# Balancing_FETs.net
KiCad netlist of a schematic drawn in Altium Designer
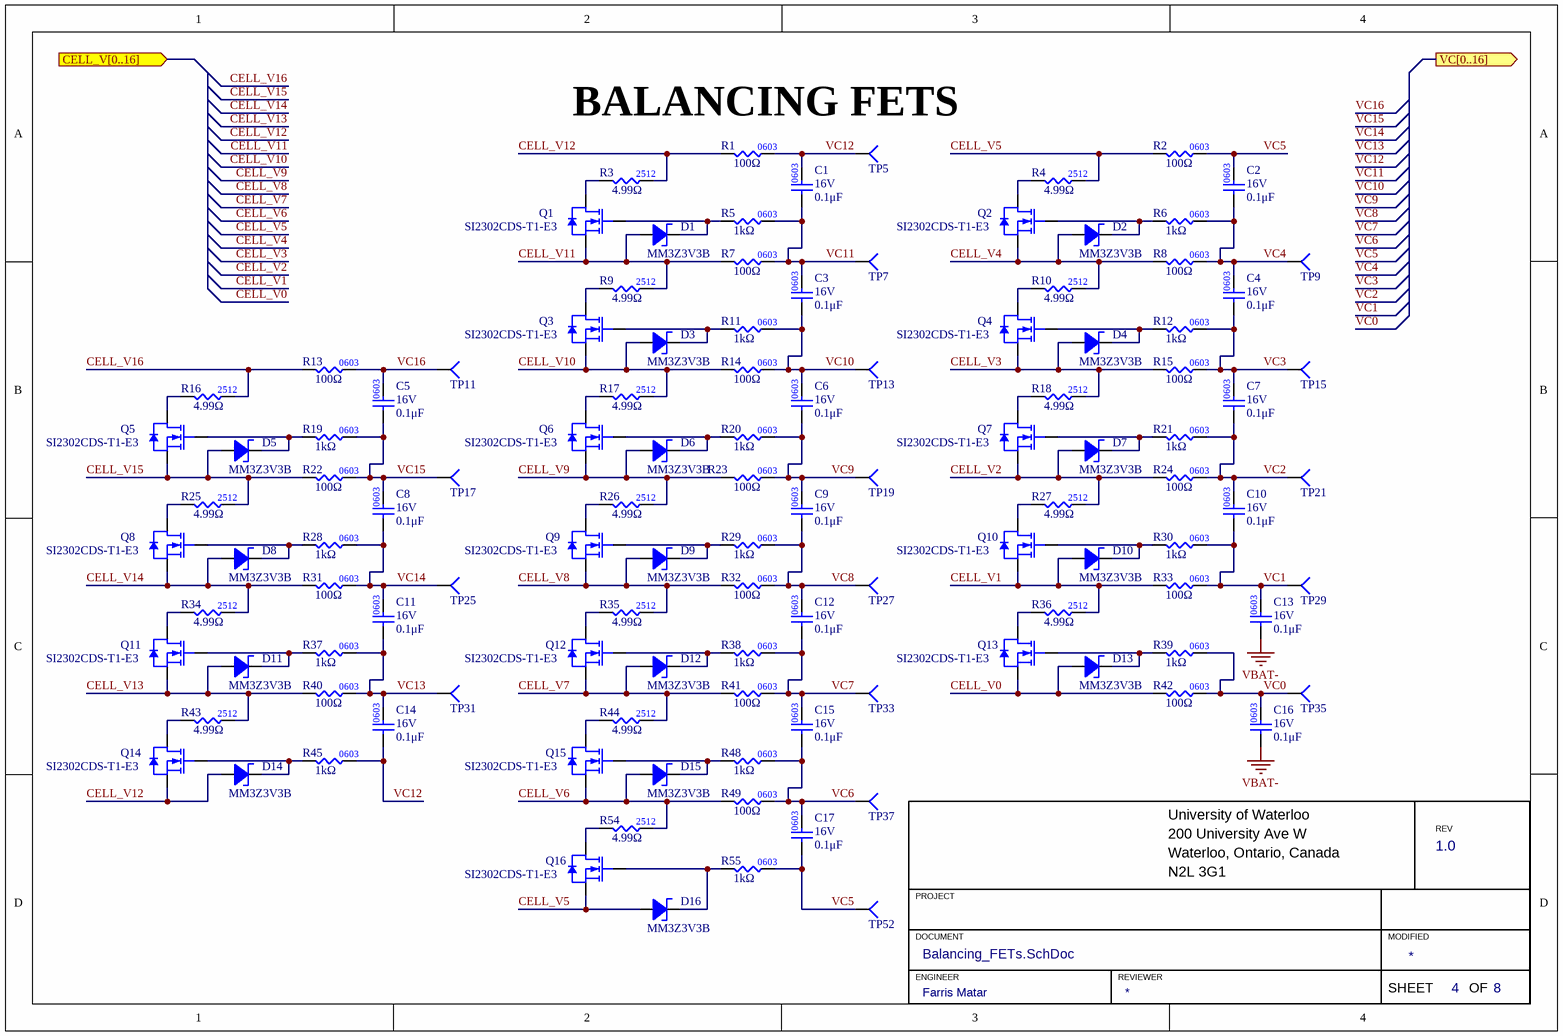
[diagram p0: Balancing_FETs.SchDoc]

(export (version "E")
  (design (tool "Eeschema 10.0.6"))
  (components
    (comp (ref "C1")
      (value "0.1μF")
      (footprint "CAP0603")
      (description "CAP CER 0.1UF 16V X7R 0603")
      (fields (field (name "VOLTAGE RATING") "16V") (field (name "Comment") "CAP_0.1uF_16V_0603"))
      (libsource (lib "Personal_Schematic_Library_2022") (part "CAP_0.1uF_16V_0603"))
    )
    (comp (ref "C2")
      (value "0.1μF")
      (footprint "CAP0603")
      (description "CAP CER 0.1UF 16V X7R 0603")
      (fields (field (name "VOLTAGE RATING") "16V") (field (name "Comment") "CAP_0.1uF_16V_0603"))
      (libsource (lib "Personal_Schematic_Library_2022") (part "CAP_0.1uF_16V_0603"))
    )
    (comp (ref "C3")
      (value "0.1μF")
      (footprint "CAP0603")
      (description "CAP CER 0.1UF 16V X7R 0603")
      (fields (field (name "VOLTAGE RATING") "16V") (field (name "Comment") "CAP_0.1uF_16V_0603"))
      (libsource (lib "Personal_Schematic_Library_2022") (part "CAP_0.1uF_16V_0603"))
    )
    (comp (ref "C4")
      (value "0.1μF")
      (footprint "CAP0603")
      (description "CAP CER 0.1UF 16V X7R 0603")
      (fields (field (name "VOLTAGE RATING") "16V") (field (name "Comment") "CAP_0.1uF_16V_0603"))
      (libsource (lib "Personal_Schematic_Library_2022") (part "CAP_0.1uF_16V_0603"))
    )
    (comp (ref "C5")
      (value "0.1μF")
      (footprint "CAP0603")
      (description "CAP CER 0.1UF 16V X7R 0603")
      (fields (field (name "VOLTAGE RATING") "16V") (field (name "Comment") "CAP_0.1uF_16V_0603"))
      (libsource (lib "Personal_Schematic_Library_2022") (part "CAP_0.1uF_16V_0603"))
    )
    (comp (ref "C6")
      (value "0.1μF")
      (footprint "CAP0603")
      (description "CAP CER 0.1UF 16V X7R 0603")
      (fields (field (name "VOLTAGE RATING") "16V") (field (name "Comment") "CAP_0.1uF_16V_0603"))
      (libsource (lib "Personal_Schematic_Library_2022") (part "CAP_0.1uF_16V_0603"))
    )
    (comp (ref "C7")
      (value "0.1μF")
      (footprint "CAP0603")
      (description "CAP CER 0.1UF 16V X7R 0603")
      (fields (field (name "VOLTAGE RATING") "16V") (field (name "Comment") "CAP_0.1uF_16V_0603"))
      (libsource (lib "Personal_Schematic_Library_2022") (part "CAP_0.1uF_16V_0603"))
    )
    (comp (ref "C8")
      (value "0.1μF")
      (footprint "CAP0603")
      (description "CAP CER 0.1UF 16V X7R 0603")
      (fields (field (name "VOLTAGE RATING") "16V") (field (name "Comment") "CAP_0.1uF_16V_0603"))
      (libsource (lib "Personal_Schematic_Library_2022") (part "CAP_0.1uF_16V_0603"))
    )
    (comp (ref "C9")
      (value "0.1μF")
      (footprint "CAP0603")
      (description "CAP CER 0.1UF 16V X7R 0603")
      (fields (field (name "VOLTAGE RATING") "16V") (field (name "Comment") "CAP_0.1uF_16V_0603"))
      (libsource (lib "Personal_Schematic_Library_2022") (part "CAP_0.1uF_16V_0603"))
    )
    (comp (ref "C10")
      (value "0.1μF")
      (footprint "CAP0603")
      (description "CAP CER 0.1UF 16V X7R 0603")
      (fields (field (name "VOLTAGE RATING") "16V") (field (name "Comment") "CAP_0.1uF_16V_0603"))
      (libsource (lib "Personal_Schematic_Library_2022") (part "CAP_0.1uF_16V_0603"))
    )
    (comp (ref "C11")
      (value "0.1μF")
      (footprint "CAP0603")
      (description "CAP CER 0.1UF 16V X7R 0603")
      (fields (field (name "VOLTAGE RATING") "16V") (field (name "Comment") "CAP_0.1uF_16V_0603"))
      (libsource (lib "Personal_Schematic_Library_2022") (part "CAP_0.1uF_16V_0603"))
    )
    (comp (ref "C12")
      (value "0.1μF")
      (footprint "CAP0603")
      (description "CAP CER 0.1UF 16V X7R 0603")
      (fields (field (name "VOLTAGE RATING") "16V") (field (name "Comment") "CAP_0.1uF_16V_0603"))
      (libsource (lib "Personal_Schematic_Library_2022") (part "CAP_0.1uF_16V_0603"))
    )
    (comp (ref "C13")
      (value "0.1μF")
      (footprint "CAP0603")
      (description "CAP CER 0.1UF 16V X7R 0603")
      (fields (field (name "VOLTAGE RATING") "16V") (field (name "Comment") "CAP_0.1uF_16V_0603"))
      (libsource (lib "Personal_Schematic_Library_2022") (part "CAP_0.1uF_16V_0603"))
    )
    (comp (ref "C14")
      (value "0.1μF")
      (footprint "CAP0603")
      (description "CAP CER 0.1UF 16V X7R 0603")
      (fields (field (name "VOLTAGE RATING") "16V") (field (name "Comment") "CAP_0.1uF_16V_0603"))
      (libsource (lib "Personal_Schematic_Library_2022") (part "CAP_0.1uF_16V_0603"))
    )
    (comp (ref "C15")
      (value "0.1μF")
      (footprint "CAP0603")
      (description "CAP CER 0.1UF 16V X7R 0603")
      (fields (field (name "VOLTAGE RATING") "16V") (field (name "Comment") "CAP_0.1uF_16V_0603"))
      (libsource (lib "Personal_Schematic_Library_2022") (part "CAP_0.1uF_16V_0603"))
    )
    (comp (ref "C16")
      (value "0.1μF")
      (footprint "CAP0603")
      (description "CAP CER 0.1UF 16V X7R 0603")
      (fields (field (name "VOLTAGE RATING") "16V") (field (name "Comment") "CAP_0.1uF_16V_0603"))
      (libsource (lib "Personal_Schematic_Library_2022") (part "CAP_0.1uF_16V_0603"))
    )
    (comp (ref "C17")
      (value "0.1μF")
      (footprint "CAP0603")
      (description "CAP CER 0.1UF 16V X7R 0603")
      (fields (field (name "VOLTAGE RATING") "16V") (field (name "Comment") "CAP_0.1uF_16V_0603"))
      (libsource (lib "Personal_Schematic_Library_2022") (part "CAP_0.1uF_16V_0603"))
    )
    (comp (ref "D1")
      (value "DIO_ZENER_3V3")
      (footprint "DIO_ZENER_3V3")
      (description "DIODE ZENER 3.3V 200mW SOD323F")
      (fields (field (name "MANUFACTURER PART NUMBER 1") "MM3Z3V3B"))
      (libsource (lib "Personal_Schematic_Library_2022") (part "DIO_ZENER_3V3"))
    )
    (comp (ref "D2")
      (value "DIO_ZENER_3V3")
      (footprint "DIO_ZENER_3V3")
      (description "DIODE ZENER 3.3V 200mW SOD323F")
      (fields (field (name "MANUFACTURER PART NUMBER 1") "MM3Z3V3B"))
      (libsource (lib "Personal_Schematic_Library_2022") (part "DIO_ZENER_3V3"))
    )
    (comp (ref "D3")
      (value "DIO_ZENER_3V3")
      (footprint "DIO_ZENER_3V3")
      (description "DIODE ZENER 3.3V 200mW SOD323F")
      (fields (field (name "MANUFACTURER PART NUMBER 1") "MM3Z3V3B"))
      (libsource (lib "Personal_Schematic_Library_2022") (part "DIO_ZENER_3V3"))
    )
    (comp (ref "D4")
      (value "DIO_ZENER_3V3")
      (footprint "DIO_ZENER_3V3")
      (description "DIODE ZENER 3.3V 200mW SOD323F")
      (fields (field (name "MANUFACTURER PART NUMBER 1") "MM3Z3V3B"))
      (libsource (lib "Personal_Schematic_Library_2022") (part "DIO_ZENER_3V3"))
    )
    (comp (ref "D5")
      (value "DIO_ZENER_3V3")
      (footprint "DIO_ZENER_3V3")
      (description "DIODE ZENER 3.3V 200mW SOD323F")
      (fields (field (name "MANUFACTURER PART NUMBER 1") "MM3Z3V3B"))
      (libsource (lib "Personal_Schematic_Library_2022") (part "DIO_ZENER_3V3"))
    )
    (comp (ref "D6")
      (value "DIO_ZENER_3V3")
      (footprint "DIO_ZENER_3V3")
      (description "DIODE ZENER 3.3V 200mW SOD323F")
      (fields (field (name "MANUFACTURER PART NUMBER 1") "MM3Z3V3B"))
      (libsource (lib "Personal_Schematic_Library_2022") (part "DIO_ZENER_3V3"))
    )
    (comp (ref "D7")
      (value "DIO_ZENER_3V3")
      (footprint "DIO_ZENER_3V3")
      (description "DIODE ZENER 3.3V 200mW SOD323F")
      (fields (field (name "MANUFACTURER PART NUMBER 1") "MM3Z3V3B"))
      (libsource (lib "Personal_Schematic_Library_2022") (part "DIO_ZENER_3V3"))
    )
    (comp (ref "D8")
      (value "DIO_ZENER_3V3")
      (footprint "DIO_ZENER_3V3")
      (description "DIODE ZENER 3.3V 200mW SOD323F")
      (fields (field (name "MANUFACTURER PART NUMBER 1") "MM3Z3V3B"))
      (libsource (lib "Personal_Schematic_Library_2022") (part "DIO_ZENER_3V3"))
    )
    (comp (ref "D9")
      (value "DIO_ZENER_3V3")
      (footprint "DIO_ZENER_3V3")
      (description "DIODE ZENER 3.3V 200mW SOD323F")
      (fields (field (name "MANUFACTURER PART NUMBER 1") "MM3Z3V3B"))
      (libsource (lib "Personal_Schematic_Library_2022") (part "DIO_ZENER_3V3"))
    )
    (comp (ref "D10")
      (value "DIO_ZENER_3V3")
      (footprint "DIO_ZENER_3V3")
      (description "DIODE ZENER 3.3V 200mW SOD323F")
      (fields (field (name "MANUFACTURER PART NUMBER 1") "MM3Z3V3B"))
      (libsource (lib "Personal_Schematic_Library_2022") (part "DIO_ZENER_3V3"))
    )
    (comp (ref "D11")
      (value "DIO_ZENER_3V3")
      (footprint "DIO_ZENER_3V3")
      (description "DIODE ZENER 3.3V 200mW SOD323F")
      (fields (field (name "MANUFACTURER PART NUMBER 1") "MM3Z3V3B"))
      (libsource (lib "Personal_Schematic_Library_2022") (part "DIO_ZENER_3V3"))
    )
    (comp (ref "D12")
      (value "DIO_ZENER_3V3")
      (footprint "DIO_ZENER_3V3")
      (description "DIODE ZENER 3.3V 200mW SOD323F")
      (fields (field (name "MANUFACTURER PART NUMBER 1") "MM3Z3V3B"))
      (libsource (lib "Personal_Schematic_Library_2022") (part "DIO_ZENER_3V3"))
    )
    (comp (ref "D13")
      (value "DIO_ZENER_3V3")
      (footprint "DIO_ZENER_3V3")
      (description "DIODE ZENER 3.3V 200mW SOD323F")
      (fields (field (name "MANUFACTURER PART NUMBER 1") "MM3Z3V3B"))
      (libsource (lib "Personal_Schematic_Library_2022") (part "DIO_ZENER_3V3"))
    )
    (comp (ref "D14")
      (value "DIO_ZENER_3V3")
      (footprint "DIO_ZENER_3V3")
      (description "DIODE ZENER 3.3V 200mW SOD323F")
      (fields (field (name "MANUFACTURER PART NUMBER 1") "MM3Z3V3B"))
      (libsource (lib "Personal_Schematic_Library_2022") (part "DIO_ZENER_3V3"))
    )
    (comp (ref "D15")
      (value "DIO_ZENER_3V3")
      (footprint "DIO_ZENER_3V3")
      (description "DIODE ZENER 3.3V 200mW SOD323F")
      (fields (field (name "MANUFACTURER PART NUMBER 1") "MM3Z3V3B"))
      (libsource (lib "Personal_Schematic_Library_2022") (part "DIO_ZENER_3V3"))
    )
    (comp (ref "D16")
      (value "DIO_ZENER_3V3")
      (footprint "DIO_ZENER_3V3")
      (description "DIODE ZENER 3.3V 200mW SOD323F")
      (fields (field (name "MANUFACTURER PART NUMBER 1") "MM3Z3V3B"))
      (libsource (lib "Personal_Schematic_Library_2022") (part "DIO_ZENER_3V3"))
    )
    (comp (ref "Q1")
      (value "NMOS_20V_6A")
      (footprint "SOT23-3")
      (description "MOSFET N-CH 20V 2.6A SOT23-3")
      (fields (field (name "MANUFACTURER PART NUMBER 1") "SI2302CDS-T1-E3"))
      (libsource (lib "Personal_Schematic_Library_2022") (part "NMOS_20V_2.6A"))
    )
    (comp (ref "Q2")
      (value "NMOS_20V_6A")
      (footprint "SOT23-3")
      (description "MOSFET N-CH 20V 2.6A SOT23-3")
      (fields (field (name "MANUFACTURER PART NUMBER 1") "SI2302CDS-T1-E3"))
      (libsource (lib "Personal_Schematic_Library_2022") (part "NMOS_20V_2.6A"))
    )
    (comp (ref "Q3")
      (value "NMOS_20V_6A")
      (footprint "SOT23-3")
      (description "MOSFET N-CH 20V 2.6A SOT23-3")
      (fields (field (name "MANUFACTURER PART NUMBER 1") "SI2302CDS-T1-E3"))
      (libsource (lib "Personal_Schematic_Library_2022") (part "NMOS_20V_2.6A"))
    )
    (comp (ref "Q4")
      (value "NMOS_20V_6A")
      (footprint "SOT23-3")
      (description "MOSFET N-CH 20V 2.6A SOT23-3")
      (fields (field (name "MANUFACTURER PART NUMBER 1") "SI2302CDS-T1-E3"))
      (libsource (lib "Personal_Schematic_Library_2022") (part "NMOS_20V_2.6A"))
    )
    (comp (ref "Q5")
      (value "NMOS_20V_6A")
      (footprint "SOT23-3")
      (description "MOSFET N-CH 20V 2.6A SOT23-3")
      (fields (field (name "MANUFACTURER PART NUMBER 1") "SI2302CDS-T1-E3"))
      (libsource (lib "Personal_Schematic_Library_2022") (part "NMOS_20V_2.6A"))
    )
    (comp (ref "Q6")
      (value "NMOS_20V_6A")
      (footprint "SOT23-3")
      (description "MOSFET N-CH 20V 2.6A SOT23-3")
      (fields (field (name "MANUFACTURER PART NUMBER 1") "SI2302CDS-T1-E3"))
      (libsource (lib "Personal_Schematic_Library_2022") (part "NMOS_20V_2.6A"))
    )
    (comp (ref "Q7")
      (value "NMOS_20V_6A")
      (footprint "SOT23-3")
      (description "MOSFET N-CH 20V 2.6A SOT23-3")
      (fields (field (name "MANUFACTURER PART NUMBER 1") "SI2302CDS-T1-E3"))
      (libsource (lib "Personal_Schematic_Library_2022") (part "NMOS_20V_2.6A"))
    )
    (comp (ref "Q8")
      (value "NMOS_20V_6A")
      (footprint "SOT23-3")
      (description "MOSFET N-CH 20V 2.6A SOT23-3")
      (fields (field (name "MANUFACTURER PART NUMBER 1") "SI2302CDS-T1-E3"))
      (libsource (lib "Personal_Schematic_Library_2022") (part "NMOS_20V_2.6A"))
    )
    (comp (ref "Q9")
      (value "NMOS_20V_6A")
      (footprint "SOT23-3")
      (description "MOSFET N-CH 20V 2.6A SOT23-3")
      (fields (field (name "MANUFACTURER PART NUMBER 1") "SI2302CDS-T1-E3"))
      (libsource (lib "Personal_Schematic_Library_2022") (part "NMOS_20V_2.6A"))
    )
    (comp (ref "Q10")
      (value "NMOS_20V_6A")
      (footprint "SOT23-3")
      (description "MOSFET N-CH 20V 2.6A SOT23-3")
      (fields (field (name "MANUFACTURER PART NUMBER 1") "SI2302CDS-T1-E3"))
      (libsource (lib "Personal_Schematic_Library_2022") (part "NMOS_20V_2.6A"))
    )
    (comp (ref "Q11")
      (value "NMOS_20V_6A")
      (footprint "SOT23-3")
      (description "MOSFET N-CH 20V 2.6A SOT23-3")
      (fields (field (name "MANUFACTURER PART NUMBER 1") "SI2302CDS-T1-E3"))
      (libsource (lib "Personal_Schematic_Library_2022") (part "NMOS_20V_2.6A"))
    )
    (comp (ref "Q12")
      (value "NMOS_20V_6A")
      (footprint "SOT23-3")
      (description "MOSFET N-CH 20V 2.6A SOT23-3")
      (fields (field (name "MANUFACTURER PART NUMBER 1") "SI2302CDS-T1-E3"))
      (libsource (lib "Personal_Schematic_Library_2022") (part "NMOS_20V_2.6A"))
    )
    (comp (ref "Q13")
      (value "NMOS_20V_6A")
      (footprint "SOT23-3")
      (description "MOSFET N-CH 20V 2.6A SOT23-3")
      (fields (field (name "MANUFACTURER PART NUMBER 1") "SI2302CDS-T1-E3"))
      (libsource (lib "Personal_Schematic_Library_2022") (part "NMOS_20V_2.6A"))
    )
    (comp (ref "Q14")
      (value "NMOS_20V_6A")
      (footprint "SOT23-3")
      (description "MOSFET N-CH 20V 2.6A SOT23-3")
      (fields (field (name "MANUFACTURER PART NUMBER 1") "SI2302CDS-T1-E3"))
      (libsource (lib "Personal_Schematic_Library_2022") (part "NMOS_20V_2.6A"))
    )
    (comp (ref "Q15")
      (value "NMOS_20V_6A")
      (footprint "SOT23-3")
      (description "MOSFET N-CH 20V 2.6A SOT23-3")
      (fields (field (name "MANUFACTURER PART NUMBER 1") "SI2302CDS-T1-E3"))
      (libsource (lib "Personal_Schematic_Library_2022") (part "NMOS_20V_2.6A"))
    )
    (comp (ref "Q16")
      (value "NMOS_20V_6A")
      (footprint "SOT23-3")
      (description "MOSFET N-CH 20V 2.6A SOT23-3")
      (fields (field (name "MANUFACTURER PART NUMBER 1") "SI2302CDS-T1-E3"))
      (libsource (lib "Personal_Schematic_Library_2022") (part "NMOS_20V_2.6A"))
    )
    (comp (ref "R1")
      (value "100Ω")
      (footprint "RES0603")
      (description "RES 100 OHM 1% 1/10W 0603")
      (fields (field (name "Comment") "RES_100Ω_0603_1%"))
      (libsource (lib "Personal_Schematic_Library_2022") (part "RES_100Ω_0603_1%"))
    )
    (comp (ref "R2")
      (value "100Ω")
      (footprint "RES0603")
      (description "RES 100 OHM 1% 1/10W 0603")
      (fields (field (name "Comment") "RES_100Ω_0603_1%"))
      (libsource (lib "Personal_Schematic_Library_2022") (part "RES_100Ω_0603_1%"))
    )
    (comp (ref "R3")
      (value "4.99Ω")
      (footprint "RES2512")
      (description "RES 4.99 OHM 1% 2W 2512")
      (fields (field (name "Comment") "RES_4.99Ω_2512_1%"))
      (libsource (lib "Personal_Schematic_Library_2022") (part "RES_4.99Ω_2512_1%"))
    )
    (comp (ref "R4")
      (value "4.99Ω")
      (footprint "RES2512")
      (description "RES 4.99 OHM 1% 2W 2512")
      (fields (field (name "Comment") "RES_4.99Ω_2512_1%"))
      (libsource (lib "Personal_Schematic_Library_2022") (part "RES_4.99Ω_2512_1%"))
    )
    (comp (ref "R5")
      (value "1kΩ")
      (footprint "RES0603")
      (description "RES 1K OHM 1% 1/8W 0603")
      (fields (field (name "Comment") "RES_1kΩ_0603_1%"))
      (libsource (lib "Personal_Schematic_Library_2022") (part "RES_1kΩ_0603_1%"))
    )
    (comp (ref "R6")
      (value "1kΩ")
      (footprint "RES0603")
      (description "RES 1K OHM 1% 1/8W 0603")
      (fields (field (name "Comment") "RES_1kΩ_0603_1%"))
      (libsource (lib "Personal_Schematic_Library_2022") (part "RES_1kΩ_0603_1%"))
    )
    (comp (ref "R7")
      (value "100Ω")
      (footprint "RES0603")
      (description "RES 100 OHM 1% 1/10W 0603")
      (fields (field (name "Comment") "RES_100Ω_0603_1%"))
      (libsource (lib "Personal_Schematic_Library_2022") (part "RES_100Ω_0603_1%"))
    )
    (comp (ref "R8")
      (value "100Ω")
      (footprint "RES0603")
      (description "RES 100 OHM 1% 1/10W 0603")
      (fields (field (name "Comment") "RES_100Ω_0603_1%"))
      (libsource (lib "Personal_Schematic_Library_2022") (part "RES_100Ω_0603_1%"))
    )
    (comp (ref "R9")
      (value "4.99Ω")
      (footprint "RES2512")
      (description "RES 4.99 OHM 1% 2W 2512")
      (fields (field (name "Comment") "RES_4.99Ω_2512_1%"))
      (libsource (lib "Personal_Schematic_Library_2022") (part "RES_4.99Ω_2512_1%"))
    )
    (comp (ref "R10")
      (value "4.99Ω")
      (footprint "RES2512")
      (description "RES 4.99 OHM 1% 2W 2512")
      (fields (field (name "Comment") "RES_4.99Ω_2512_1%"))
      (libsource (lib "Personal_Schematic_Library_2022") (part "RES_4.99Ω_2512_1%"))
    )
    (comp (ref "R11")
      (value "1kΩ")
      (footprint "RES0603")
      (description "RES 1K OHM 1% 1/8W 0603")
      (fields (field (name "Comment") "RES_1kΩ_0603_1%"))
      (libsource (lib "Personal_Schematic_Library_2022") (part "RES_1kΩ_0603_1%"))
    )
    (comp (ref "R12")
      (value "1kΩ")
      (footprint "RES0603")
      (description "RES 1K OHM 1% 1/8W 0603")
      (fields (field (name "Comment") "RES_1kΩ_0603_1%"))
      (libsource (lib "Personal_Schematic_Library_2022") (part "RES_1kΩ_0603_1%"))
    )
    (comp (ref "R13")
      (value "100Ω")
      (footprint "RES0603")
      (description "RES 100 OHM 1% 1/10W 0603")
      (fields (field (name "Comment") "RES_100Ω_0603_1%"))
      (libsource (lib "Personal_Schematic_Library_2022") (part "RES_100Ω_0603_1%"))
    )
    (comp (ref "R14")
      (value "100Ω")
      (footprint "RES0603")
      (description "RES 100 OHM 1% 1/10W 0603")
      (fields (field (name "Comment") "RES_100Ω_0603_1%"))
      (libsource (lib "Personal_Schematic_Library_2022") (part "RES_100Ω_0603_1%"))
    )
    (comp (ref "R15")
      (value "100Ω")
      (footprint "RES0603")
      (description "RES 100 OHM 1% 1/10W 0603")
      (fields (field (name "Comment") "RES_100Ω_0603_1%"))
      (libsource (lib "Personal_Schematic_Library_2022") (part "RES_100Ω_0603_1%"))
    )
    (comp (ref "R16")
      (value "4.99Ω")
      (footprint "RES2512")
      (description "RES 4.99 OHM 1% 2W 2512")
      (fields (field (name "Comment") "RES_4.99Ω_2512_1%"))
      (libsource (lib "Personal_Schematic_Library_2022") (part "RES_4.99Ω_2512_1%"))
    )
    (comp (ref "R17")
      (value "4.99Ω")
      (footprint "RES2512")
      (description "RES 4.99 OHM 1% 2W 2512")
      (fields (field (name "Comment") "RES_4.99Ω_2512_1%"))
      (libsource (lib "Personal_Schematic_Library_2022") (part "RES_4.99Ω_2512_1%"))
    )
    (comp (ref "R18")
      (value "4.99Ω")
      (footprint "RES2512")
      (description "RES 4.99 OHM 1% 2W 2512")
      (fields (field (name "Comment") "RES_4.99Ω_2512_1%"))
      (libsource (lib "Personal_Schematic_Library_2022") (part "RES_4.99Ω_2512_1%"))
    )
    (comp (ref "R19")
      (value "1kΩ")
      (footprint "RES0603")
      (description "RES 1K OHM 1% 1/8W 0603")
      (fields (field (name "Comment") "RES_1kΩ_0603_1%"))
      (libsource (lib "Personal_Schematic_Library_2022") (part "RES_1kΩ_0603_1%"))
    )
    (comp (ref "R20")
      (value "1kΩ")
      (footprint "RES0603")
      (description "RES 1K OHM 1% 1/8W 0603")
      (fields (field (name "Comment") "RES_1kΩ_0603_1%"))
      (libsource (lib "Personal_Schematic_Library_2022") (part "RES_1kΩ_0603_1%"))
    )
    (comp (ref "R21")
      (value "1kΩ")
      (footprint "RES0603")
      (description "RES 1K OHM 1% 1/8W 0603")
      (fields (field (name "Comment") "RES_1kΩ_0603_1%"))
      (libsource (lib "Personal_Schematic_Library_2022") (part "RES_1kΩ_0603_1%"))
    )
    (comp (ref "R22")
      (value "100Ω")
      (footprint "RES0603")
      (description "RES 100 OHM 1% 1/10W 0603")
      (fields (field (name "Comment") "RES_100Ω_0603_1%"))
      (libsource (lib "Personal_Schematic_Library_2022") (part "RES_100Ω_0603_1%"))
    )
    (comp (ref "R23")
      (value "100Ω")
      (footprint "RES0603")
      (description "RES 100 OHM 1% 1/10W 0603")
      (fields (field (name "Comment") "RES_100Ω_0603_1%"))
      (libsource (lib "Personal_Schematic_Library_2022") (part "RES_100Ω_0603_1%"))
    )
    (comp (ref "R24")
      (value "100Ω")
      (footprint "RES0603")
      (description "RES 100 OHM 1% 1/10W 0603")
      (fields (field (name "Comment") "RES_100Ω_0603_1%"))
      (libsource (lib "Personal_Schematic_Library_2022") (part "RES_100Ω_0603_1%"))
    )
    (comp (ref "R25")
      (value "4.99Ω")
      (footprint "RES2512")
      (description "RES 4.99 OHM 1% 2W 2512")
      (fields (field (name "Comment") "RES_4.99Ω_2512_1%"))
      (libsource (lib "Personal_Schematic_Library_2022") (part "RES_4.99Ω_2512_1%"))
    )
    (comp (ref "R26")
      (value "4.99Ω")
      (footprint "RES2512")
      (description "RES 4.99 OHM 1% 2W 2512")
      (fields (field (name "Comment") "RES_4.99Ω_2512_1%"))
      (libsource (lib "Personal_Schematic_Library_2022") (part "RES_4.99Ω_2512_1%"))
    )
    (comp (ref "R27")
      (value "4.99Ω")
      (footprint "RES2512")
      (description "RES 4.99 OHM 1% 2W 2512")
      (fields (field (name "Comment") "RES_4.99Ω_2512_1%"))
      (libsource (lib "Personal_Schematic_Library_2022") (part "RES_4.99Ω_2512_1%"))
    )
    (comp (ref "R28")
      (value "1kΩ")
      (footprint "RES0603")
      (description "RES 1K OHM 1% 1/8W 0603")
      (fields (field (name "Comment") "RES_1kΩ_0603_1%"))
      (libsource (lib "Personal_Schematic_Library_2022") (part "RES_1kΩ_0603_1%"))
    )
    (comp (ref "R29")
      (value "1kΩ")
      (footprint "RES0603")
      (description "RES 1K OHM 1% 1/8W 0603")
      (fields (field (name "Comment") "RES_1kΩ_0603_1%"))
      (libsource (lib "Personal_Schematic_Library_2022") (part "RES_1kΩ_0603_1%"))
    )
    (comp (ref "R30")
      (value "1kΩ")
      (footprint "RES0603")
      (description "RES 1K OHM 1% 1/8W 0603")
      (fields (field (name "Comment") "RES_1kΩ_0603_1%"))
      (libsource (lib "Personal_Schematic_Library_2022") (part "RES_1kΩ_0603_1%"))
    )
    (comp (ref "R31")
      (value "100Ω")
      (footprint "RES0603")
      (description "RES 100 OHM 1% 1/10W 0603")
      (fields (field (name "Comment") "RES_100Ω_0603_1%"))
      (libsource (lib "Personal_Schematic_Library_2022") (part "RES_100Ω_0603_1%"))
    )
    (comp (ref "R32")
      (value "100Ω")
      (footprint "RES0603")
      (description "RES 100 OHM 1% 1/10W 0603")
      (fields (field (name "Comment") "RES_100Ω_0603_1%"))
      (libsource (lib "Personal_Schematic_Library_2022") (part "RES_100Ω_0603_1%"))
    )
    (comp (ref "R33")
      (value "100Ω")
      (footprint "RES0603")
      (description "RES 100 OHM 1% 1/10W 0603")
      (fields (field (name "Comment") "RES_100Ω_0603_1%"))
      (libsource (lib "Personal_Schematic_Library_2022") (part "RES_100Ω_0603_1%"))
    )
    (comp (ref "R34")
      (value "4.99Ω")
      (footprint "RES2512")
      (description "RES 4.99 OHM 1% 2W 2512")
      (fields (field (name "Comment") "RES_4.99Ω_2512_1%"))
      (libsource (lib "Personal_Schematic_Library_2022") (part "RES_4.99Ω_2512_1%"))
    )
    (comp (ref "R35")
      (value "4.99Ω")
      (footprint "RES2512")
      (description "RES 4.99 OHM 1% 2W 2512")
      (fields (field (name "Comment") "RES_4.99Ω_2512_1%"))
      (libsource (lib "Personal_Schematic_Library_2022") (part "RES_4.99Ω_2512_1%"))
    )
    (comp (ref "R36")
      (value "4.99Ω")
      (footprint "RES2512")
      (description "RES 4.99 OHM 1% 2W 2512")
      (fields (field (name "Comment") "RES_4.99Ω_2512_1%"))
      (libsource (lib "Personal_Schematic_Library_2022") (part "RES_4.99Ω_2512_1%"))
    )
    (comp (ref "R37")
      (value "1kΩ")
      (footprint "RES0603")
      (description "RES 1K OHM 1% 1/8W 0603")
      (fields (field (name "Comment") "RES_1kΩ_0603_1%"))
      (libsource (lib "Personal_Schematic_Library_2022") (part "RES_1kΩ_0603_1%"))
    )
    (comp (ref "R38")
      (value "1kΩ")
      (footprint "RES0603")
      (description "RES 1K OHM 1% 1/8W 0603")
      (fields (field (name "Comment") "RES_1kΩ_0603_1%"))
      (libsource (lib "Personal_Schematic_Library_2022") (part "RES_1kΩ_0603_1%"))
    )
    (comp (ref "R39")
      (value "1kΩ")
      (footprint "RES0603")
      (description "RES 1K OHM 1% 1/8W 0603")
      (fields (field (name "Comment") "RES_1kΩ_0603_1%"))
      (libsource (lib "Personal_Schematic_Library_2022") (part "RES_1kΩ_0603_1%"))
    )
    (comp (ref "R40")
      (value "100Ω")
      (footprint "RES0603")
      (description "RES 100 OHM 1% 1/10W 0603")
      (fields (field (name "Comment") "RES_100Ω_0603_1%"))
      (libsource (lib "Personal_Schematic_Library_2022") (part "RES_100Ω_0603_1%"))
    )
    (comp (ref "R41")
      (value "100Ω")
      (footprint "RES0603")
      (description "RES 100 OHM 1% 1/10W 0603")
      (fields (field (name "Comment") "RES_100Ω_0603_1%"))
      (libsource (lib "Personal_Schematic_Library_2022") (part "RES_100Ω_0603_1%"))
    )
    (comp (ref "R42")
      (value "100Ω")
      (footprint "RES0603")
      (description "RES 100 OHM 1% 1/10W 0603")
      (fields (field (name "Comment") "RES_100Ω_0603_1%"))
      (libsource (lib "Personal_Schematic_Library_2022") (part "RES_100Ω_0603_1%"))
    )
    (comp (ref "R43")
      (value "4.99Ω")
      (footprint "RES2512")
      (description "RES 4.99 OHM 1% 2W 2512")
      (fields (field (name "Comment") "RES_4.99Ω_2512_1%"))
      (libsource (lib "Personal_Schematic_Library_2022") (part "RES_4.99Ω_2512_1%"))
    )
    (comp (ref "R44")
      (value "4.99Ω")
      (footprint "RES2512")
      (description "RES 4.99 OHM 1% 2W 2512")
      (fields (field (name "Comment") "RES_4.99Ω_2512_1%"))
      (libsource (lib "Personal_Schematic_Library_2022") (part "RES_4.99Ω_2512_1%"))
    )
    (comp (ref "R45")
      (value "1kΩ")
      (footprint "RES0603")
      (description "RES 1K OHM 1% 1/8W 0603")
      (fields (field (name "Comment") "RES_1kΩ_0603_1%"))
      (libsource (lib "Personal_Schematic_Library_2022") (part "RES_1kΩ_0603_1%"))
    )
    (comp (ref "R48")
      (value "1kΩ")
      (footprint "RES0603")
      (description "RES 1K OHM 1% 1/8W 0603")
      (fields (field (name "Comment") "RES_1kΩ_0603_1%"))
      (libsource (lib "Personal_Schematic_Library_2022") (part "RES_1kΩ_0603_1%"))
    )
    (comp (ref "R49")
      (value "100Ω")
      (footprint "RES0603")
      (description "RES 100 OHM 1% 1/10W 0603")
      (fields (field (name "Comment") "RES_100Ω_0603_1%"))
      (libsource (lib "Personal_Schematic_Library_2022") (part "RES_100Ω_0603_1%"))
    )
    (comp (ref "R54")
      (value "4.99Ω")
      (footprint "RES2512")
      (description "RES 4.99 OHM 1% 2W 2512")
      (fields (field (name "Comment") "RES_4.99Ω_2512_1%"))
      (libsource (lib "Personal_Schematic_Library_2022") (part "RES_4.99Ω_2512_1%"))
    )
    (comp (ref "R55")
      (value "1kΩ")
      (footprint "RES0603")
      (description "RES 1K OHM 1% 1/8W 0603")
      (fields (field (name "Comment") "RES_1kΩ_0603_1%"))
      (libsource (lib "Personal_Schematic_Library_2022") (part "RES_1kΩ_0603_1%"))
    )
    (comp (ref "TP5")
      (value "TESTPOINT_1MM_SQUARE")
      (footprint "TESTPOINT_SQUARE_1MM")
      (description "TESTPOINT 1MM SQUARE")
      (libsource (lib "Personal_Schematic_Library_2022") (part "TESTPOINT_1MM_SQUARE"))
    )
    (comp (ref "TP7")
      (value "TESTPOINT_1MM_SQUARE")
      (footprint "TESTPOINT_SQUARE_1MM")
      (description "TESTPOINT 1MM SQUARE")
      (libsource (lib "Personal_Schematic_Library_2022") (part "TESTPOINT_1MM_SQUARE"))
    )
    (comp (ref "TP9")
      (value "TESTPOINT_1MM_SQUARE")
      (footprint "TESTPOINT_SQUARE_1MM")
      (description "TESTPOINT 1MM SQUARE")
      (libsource (lib "Personal_Schematic_Library_2022") (part "TESTPOINT_1MM_SQUARE"))
    )
    (comp (ref "TP11")
      (value "TESTPOINT_1MM_SQUARE")
      (footprint "TESTPOINT_SQUARE_1MM")
      (description "TESTPOINT 1MM SQUARE")
      (libsource (lib "Personal_Schematic_Library_2022") (part "TESTPOINT_1MM_SQUARE"))
    )
    (comp (ref "TP13")
      (value "TESTPOINT_1MM_SQUARE")
      (footprint "TESTPOINT_SQUARE_1MM")
      (description "TESTPOINT 1MM SQUARE")
      (libsource (lib "Personal_Schematic_Library_2022") (part "TESTPOINT_1MM_SQUARE"))
    )
    (comp (ref "TP15")
      (value "TESTPOINT_1MM_SQUARE")
      (footprint "TESTPOINT_SQUARE_1MM")
      (description "TESTPOINT 1MM SQUARE")
      (libsource (lib "Personal_Schematic_Library_2022") (part "TESTPOINT_1MM_SQUARE"))
    )
    (comp (ref "TP17")
      (value "TESTPOINT_1MM_SQUARE")
      (footprint "TESTPOINT_SQUARE_1MM")
      (description "TESTPOINT 1MM SQUARE")
      (libsource (lib "Personal_Schematic_Library_2022") (part "TESTPOINT_1MM_SQUARE"))
    )
    (comp (ref "TP19")
      (value "TESTPOINT_1MM_SQUARE")
      (footprint "TESTPOINT_SQUARE_1MM")
      (description "TESTPOINT 1MM SQUARE")
      (libsource (lib "Personal_Schematic_Library_2022") (part "TESTPOINT_1MM_SQUARE"))
    )
    (comp (ref "TP21")
      (value "TESTPOINT_1MM_SQUARE")
      (footprint "TESTPOINT_SQUARE_1MM")
      (description "TESTPOINT 1MM SQUARE")
      (libsource (lib "Personal_Schematic_Library_2022") (part "TESTPOINT_1MM_SQUARE"))
    )
    (comp (ref "TP25")
      (value "TESTPOINT_1MM_SQUARE")
      (footprint "TESTPOINT_SQUARE_1MM")
      (description "TESTPOINT 1MM SQUARE")
      (libsource (lib "Personal_Schematic_Library_2022") (part "TESTPOINT_1MM_SQUARE"))
    )
    (comp (ref "TP27")
      (value "TESTPOINT_1MM_SQUARE")
      (footprint "TESTPOINT_SQUARE_1MM")
      (description "TESTPOINT 1MM SQUARE")
      (libsource (lib "Personal_Schematic_Library_2022") (part "TESTPOINT_1MM_SQUARE"))
    )
    (comp (ref "TP29")
      (value "TESTPOINT_1MM_SQUARE")
      (footprint "TESTPOINT_SQUARE_1MM")
      (description "TESTPOINT 1MM SQUARE")
      (libsource (lib "Personal_Schematic_Library_2022") (part "TESTPOINT_1MM_SQUARE"))
    )
    (comp (ref "TP31")
      (value "TESTPOINT_1MM_SQUARE")
      (footprint "TESTPOINT_SQUARE_1MM")
      (description "TESTPOINT 1MM SQUARE")
      (libsource (lib "Personal_Schematic_Library_2022") (part "TESTPOINT_1MM_SQUARE"))
    )
    (comp (ref "TP33")
      (value "TESTPOINT_1MM_SQUARE")
      (footprint "TESTPOINT_SQUARE_1MM")
      (description "TESTPOINT 1MM SQUARE")
      (libsource (lib "Personal_Schematic_Library_2022") (part "TESTPOINT_1MM_SQUARE"))
    )
    (comp (ref "TP35")
      (value "TESTPOINT_1MM_SQUARE")
      (footprint "TESTPOINT_SQUARE_1MM")
      (description "TESTPOINT 1MM SQUARE")
      (libsource (lib "Personal_Schematic_Library_2022") (part "TESTPOINT_1MM_SQUARE"))
    )
    (comp (ref "TP37")
      (value "TESTPOINT_1MM_SQUARE")
      (footprint "TESTPOINT_SQUARE_1MM")
      (description "TESTPOINT 1MM SQUARE")
      (libsource (lib "Personal_Schematic_Library_2022") (part "TESTPOINT_1MM_SQUARE"))
    )
    (comp (ref "TP52")
      (value "TESTPOINT_1MM_SQUARE")
      (footprint "TESTPOINT_SQUARE_1MM")
      (description "TESTPOINT 1MM SQUARE")
      (libsource (lib "Personal_Schematic_Library_2022") (part "TESTPOINT_1MM_SQUARE"))
    )
  )
  (nets
    (net (code "1") (name "/CELL_V0") (class "Default")
      (node (ref "D13") (pin "1") (pinfunction "Anode_1") (pintype "passive"))
      (node (ref "Q13") (pin "2") (pinfunction "SOURCE_2") (pintype "passive"))
      (node (ref "R42") (pin "1") (pinfunction "1_1") (pintype "passive"))
    )
    (net (code "2") (name "/CELL_V1") (class "Default")
      (node (ref "D10") (pin "1") (pinfunction "Anode_1") (pintype "passive"))
      (node (ref "Q10") (pin "2") (pinfunction "SOURCE_2") (pintype "passive"))
      (node (ref "R33") (pin "1") (pinfunction "1_1") (pintype "passive"))
      (node (ref "R36") (pin "2") (pinfunction "2_2") (pintype "passive"))
    )
    (net (code "3") (name "/CELL_V2") (class "Default")
      (node (ref "D7") (pin "1") (pinfunction "Anode_1") (pintype "passive"))
      (node (ref "Q7") (pin "2") (pinfunction "SOURCE_2") (pintype "passive"))
      (node (ref "R24") (pin "1") (pinfunction "1_1") (pintype "passive"))
      (node (ref "R27") (pin "2") (pinfunction "2_2") (pintype "passive"))
    )
    (net (code "4") (name "/CELL_V3") (class "Default")
      (node (ref "D4") (pin "1") (pinfunction "Anode_1") (pintype "passive"))
      (node (ref "Q4") (pin "2") (pinfunction "SOURCE_2") (pintype "passive"))
      (node (ref "R15") (pin "1") (pinfunction "1_1") (pintype "passive"))
      (node (ref "R18") (pin "2") (pinfunction "2_2") (pintype "passive"))
    )
    (net (code "5") (name "/CELL_V4") (class "Default")
      (node (ref "D2") (pin "1") (pinfunction "Anode_1") (pintype "passive"))
      (node (ref "Q2") (pin "2") (pinfunction "SOURCE_2") (pintype "passive"))
      (node (ref "R10") (pin "2") (pinfunction "2_2") (pintype "passive"))
      (node (ref "R8") (pin "1") (pinfunction "1_1") (pintype "passive"))
    )
    (net (code "6") (name "/CELL_V5") (class "Default")
      (node (ref "D16") (pin "1") (pinfunction "Anode_1") (pintype "passive"))
      (node (ref "Q16") (pin "2") (pinfunction "SOURCE_2") (pintype "passive"))
      (node (ref "R2") (pin "1") (pinfunction "1_1") (pintype "passive"))
      (node (ref "R4") (pin "2") (pinfunction "2_2") (pintype "passive"))
    )
    (net (code "7") (name "/CELL_V6") (class "Default")
      (node (ref "D15") (pin "1") (pinfunction "Anode_1") (pintype "passive"))
      (node (ref "Q15") (pin "2") (pinfunction "SOURCE_2") (pintype "passive"))
      (node (ref "R49") (pin "1") (pinfunction "1_1") (pintype "passive"))
      (node (ref "R54") (pin "2") (pinfunction "2_2") (pintype "passive"))
    )
    (net (code "8") (name "/CELL_V7") (class "Default")
      (node (ref "D12") (pin "1") (pinfunction "Anode_1") (pintype "passive"))
      (node (ref "Q12") (pin "2") (pinfunction "SOURCE_2") (pintype "passive"))
      (node (ref "R41") (pin "1") (pinfunction "1_1") (pintype "passive"))
      (node (ref "R44") (pin "2") (pinfunction "2_2") (pintype "passive"))
    )
    (net (code "9") (name "/CELL_V8") (class "Default")
      (node (ref "D9") (pin "1") (pinfunction "Anode_1") (pintype "passive"))
      (node (ref "Q9") (pin "2") (pinfunction "SOURCE_2") (pintype "passive"))
      (node (ref "R32") (pin "1") (pinfunction "1_1") (pintype "passive"))
      (node (ref "R35") (pin "2") (pinfunction "2_2") (pintype "passive"))
    )
    (net (code "10") (name "/CELL_V9") (class "Default")
      (node (ref "D6") (pin "1") (pinfunction "Anode_1") (pintype "passive"))
      (node (ref "Q6") (pin "2") (pinfunction "SOURCE_2") (pintype "passive"))
      (node (ref "R23") (pin "1") (pinfunction "1_1") (pintype "passive"))
      (node (ref "R26") (pin "2") (pinfunction "2_2") (pintype "passive"))
    )
    (net (code "11") (name "/CELL_V10") (class "Default")
      (node (ref "D3") (pin "1") (pinfunction "Anode_1") (pintype "passive"))
      (node (ref "Q3") (pin "2") (pinfunction "SOURCE_2") (pintype "passive"))
      (node (ref "R14") (pin "1") (pinfunction "1_1") (pintype "passive"))
      (node (ref "R17") (pin "2") (pinfunction "2_2") (pintype "passive"))
    )
    (net (code "12") (name "/CELL_V11") (class "Default")
      (node (ref "D1") (pin "1") (pinfunction "Anode_1") (pintype "passive"))
      (node (ref "Q1") (pin "2") (pinfunction "SOURCE_2") (pintype "passive"))
      (node (ref "R7") (pin "1") (pinfunction "1_1") (pintype "passive"))
      (node (ref "R9") (pin "2") (pinfunction "2_2") (pintype "passive"))
    )
    (net (code "13") (name "/CELL_V12") (class "Default")
      (node (ref "D14") (pin "1") (pinfunction "Anode_1") (pintype "passive"))
      (node (ref "Q14") (pin "2") (pinfunction "SOURCE_2") (pintype "passive"))
      (node (ref "R1") (pin "1") (pinfunction "1_1") (pintype "passive"))
      (node (ref "R3") (pin "2") (pinfunction "2_2") (pintype "passive"))
    )
    (net (code "14") (name "/CELL_V13") (class "Default")
      (node (ref "D11") (pin "1") (pinfunction "Anode_1") (pintype "passive"))
      (node (ref "Q11") (pin "2") (pinfunction "SOURCE_2") (pintype "passive"))
      (node (ref "R40") (pin "1") (pinfunction "1_1") (pintype "passive"))
      (node (ref "R43") (pin "2") (pinfunction "2_2") (pintype "passive"))
    )
    (net (code "15") (name "/CELL_V14") (class "Default")
      (node (ref "D8") (pin "1") (pinfunction "Anode_1") (pintype "passive"))
      (node (ref "Q8") (pin "2") (pinfunction "SOURCE_2") (pintype "passive"))
      (node (ref "R31") (pin "1") (pinfunction "1_1") (pintype "passive"))
      (node (ref "R34") (pin "2") (pinfunction "2_2") (pintype "passive"))
    )
    (net (code "16") (name "/CELL_V15") (class "Default")
      (node (ref "D5") (pin "1") (pinfunction "Anode_1") (pintype "passive"))
      (node (ref "Q5") (pin "2") (pinfunction "SOURCE_2") (pintype "passive"))
      (node (ref "R22") (pin "1") (pinfunction "1_1") (pintype "passive"))
      (node (ref "R25") (pin "2") (pinfunction "2_2") (pintype "passive"))
    )
    (net (code "17") (name "/CELL_V16") (class "Default")
      (node (ref "R13") (pin "1") (pinfunction "1_1") (pintype "passive"))
      (node (ref "R16") (pin "2") (pinfunction "2_2") (pintype "passive"))
    )
    (net (code "19") (name "/VC0") (class "Default")
      (node (ref "C16") (pin "2") (pinfunction "2_2") (pintype "passive"))
      (node (ref "R39") (pin "2") (pinfunction "2_2") (pintype "passive"))
      (node (ref "R42") (pin "2") (pinfunction "2_2") (pintype "passive"))
      (node (ref "TP35") (pin "1") (pinfunction "=value_1") (pintype "passive"))
    )
    (net (code "20") (name "/VC1") (class "Default")
      (node (ref "C10") (pin "1") (pinfunction "1_1") (pintype "passive"))
      (node (ref "C13") (pin "2") (pinfunction "2_2") (pintype "passive"))
      (node (ref "R30") (pin "2") (pinfunction "2_2") (pintype "passive"))
      (node (ref "R33") (pin "2") (pinfunction "2_2") (pintype "passive"))
      (node (ref "TP29") (pin "1") (pinfunction "=value_1") (pintype "passive"))
    )
    (net (code "21") (name "/VC2") (class "Default")
      (node (ref "C10") (pin "2") (pinfunction "2_2") (pintype "passive"))
      (node (ref "C7") (pin "1") (pinfunction "1_1") (pintype "passive"))
      (node (ref "R21") (pin "2") (pinfunction "2_2") (pintype "passive"))
      (node (ref "R24") (pin "2") (pinfunction "2_2") (pintype "passive"))
      (node (ref "TP21") (pin "1") (pinfunction "=value_1") (pintype "passive"))
    )
    (net (code "22") (name "/VC3") (class "Default")
      (node (ref "C4") (pin "1") (pinfunction "1_1") (pintype "passive"))
      (node (ref "C7") (pin "2") (pinfunction "2_2") (pintype "passive"))
      (node (ref "R12") (pin "2") (pinfunction "2_2") (pintype "passive"))
      (node (ref "R15") (pin "2") (pinfunction "2_2") (pintype "passive"))
      (node (ref "TP15") (pin "1") (pinfunction "=value_1") (pintype "passive"))
    )
    (net (code "23") (name "/VC4") (class "Default")
      (node (ref "C2") (pin "1") (pinfunction "1_1") (pintype "passive"))
      (node (ref "C4") (pin "2") (pinfunction "2_2") (pintype "passive"))
      (node (ref "R6") (pin "2") (pinfunction "2_2") (pintype "passive"))
      (node (ref "R8") (pin "2") (pinfunction "2_2") (pintype "passive"))
      (node (ref "TP9") (pin "1") (pinfunction "=value_1") (pintype "passive"))
    )
    (net (code "24") (name "/VC5") (class "Default")
      (node (ref "C17") (pin "1") (pinfunction "1_1") (pintype "passive"))
      (node (ref "C2") (pin "2") (pinfunction "2_2") (pintype "passive"))
      (node (ref "R2") (pin "2") (pinfunction "2_2") (pintype "passive"))
      (node (ref "R55") (pin "2") (pinfunction "2_2") (pintype "passive"))
      (node (ref "TP52") (pin "1") (pinfunction "=value_1") (pintype "passive"))
    )
    (net (code "25") (name "/VC6") (class "Default")
      (node (ref "C15") (pin "1") (pinfunction "1_1") (pintype "passive"))
      (node (ref "C17") (pin "2") (pinfunction "2_2") (pintype "passive"))
      (node (ref "R48") (pin "2") (pinfunction "2_2") (pintype "passive"))
      (node (ref "R49") (pin "2") (pinfunction "2_2") (pintype "passive"))
      (node (ref "TP37") (pin "1") (pinfunction "=value_1") (pintype "passive"))
    )
    (net (code "26") (name "/VC7") (class "Default")
      (node (ref "C12") (pin "1") (pinfunction "1_1") (pintype "passive"))
      (node (ref "C15") (pin "2") (pinfunction "2_2") (pintype "passive"))
      (node (ref "R38") (pin "2") (pinfunction "2_2") (pintype "passive"))
      (node (ref "R41") (pin "2") (pinfunction "2_2") (pintype "passive"))
      (node (ref "TP33") (pin "1") (pinfunction "=value_1") (pintype "passive"))
    )
    (net (code "27") (name "/VC8") (class "Default")
      (node (ref "C12") (pin "2") (pinfunction "2_2") (pintype "passive"))
      (node (ref "C9") (pin "1") (pinfunction "1_1") (pintype "passive"))
      (node (ref "R29") (pin "2") (pinfunction "2_2") (pintype "passive"))
      (node (ref "R32") (pin "2") (pinfunction "2_2") (pintype "passive"))
      (node (ref "TP27") (pin "1") (pinfunction "=value_1") (pintype "passive"))
    )
    (net (code "28") (name "/VC9") (class "Default")
      (node (ref "C6") (pin "1") (pinfunction "1_1") (pintype "passive"))
      (node (ref "C9") (pin "2") (pinfunction "2_2") (pintype "passive"))
      (node (ref "R20") (pin "2") (pinfunction "2_2") (pintype "passive"))
      (node (ref "R23") (pin "2") (pinfunction "2_2") (pintype "passive"))
      (node (ref "TP19") (pin "1") (pinfunction "=value_1") (pintype "passive"))
    )
    (net (code "29") (name "/VC10") (class "Default")
      (node (ref "C3") (pin "1") (pinfunction "1_1") (pintype "passive"))
      (node (ref "C6") (pin "2") (pinfunction "2_2") (pintype "passive"))
      (node (ref "R11") (pin "2") (pinfunction "2_2") (pintype "passive"))
      (node (ref "R14") (pin "2") (pinfunction "2_2") (pintype "passive"))
      (node (ref "TP13") (pin "1") (pinfunction "=value_1") (pintype "passive"))
    )
    (net (code "30") (name "/VC11") (class "Default")
      (node (ref "C1") (pin "1") (pinfunction "1_1") (pintype "passive"))
      (node (ref "C3") (pin "2") (pinfunction "2_2") (pintype "passive"))
      (node (ref "R5") (pin "2") (pinfunction "2_2") (pintype "passive"))
      (node (ref "R7") (pin "2") (pinfunction "2_2") (pintype "passive"))
      (node (ref "TP7") (pin "1") (pinfunction "=value_1") (pintype "passive"))
    )
    (net (code "31") (name "/VC12") (class "Default")
      (node (ref "C1") (pin "2") (pinfunction "2_2") (pintype "passive"))
      (node (ref "C14") (pin "1") (pinfunction "1_1") (pintype "passive"))
      (node (ref "R1") (pin "2") (pinfunction "2_2") (pintype "passive"))
      (node (ref "R45") (pin "2") (pinfunction "2_2") (pintype "passive"))
      (node (ref "TP5") (pin "1") (pinfunction "=value_1") (pintype "passive"))
    )
    (net (code "32") (name "/VC13") (class "Default")
      (node (ref "C11") (pin "1") (pinfunction "1_1") (pintype "passive"))
      (node (ref "C14") (pin "2") (pinfunction "2_2") (pintype "passive"))
      (node (ref "R37") (pin "2") (pinfunction "2_2") (pintype "passive"))
      (node (ref "R40") (pin "2") (pinfunction "2_2") (pintype "passive"))
      (node (ref "TP31") (pin "1") (pinfunction "=value_1") (pintype "passive"))
    )
    (net (code "33") (name "/VC14") (class "Default")
      (node (ref "C11") (pin "2") (pinfunction "2_2") (pintype "passive"))
      (node (ref "C8") (pin "1") (pinfunction "1_1") (pintype "passive"))
      (node (ref "R28") (pin "2") (pinfunction "2_2") (pintype "passive"))
      (node (ref "R31") (pin "2") (pinfunction "2_2") (pintype "passive"))
      (node (ref "TP25") (pin "1") (pinfunction "=value_1") (pintype "passive"))
    )
    (net (code "34") (name "/VC15") (class "Default")
      (node (ref "C5") (pin "1") (pinfunction "1_1") (pintype "passive"))
      (node (ref "C8") (pin "2") (pinfunction "2_2") (pintype "passive"))
      (node (ref "R19") (pin "2") (pinfunction "2_2") (pintype "passive"))
      (node (ref "R22") (pin "2") (pinfunction "2_2") (pintype "passive"))
      (node (ref "TP17") (pin "1") (pinfunction "=value_1") (pintype "passive"))
    )
    (net (code "35") (name "/VC16") (class "Default")
      (node (ref "C5") (pin "2") (pinfunction "2_2") (pintype "passive"))
      (node (ref "R13") (pin "2") (pinfunction "2_2") (pintype "passive"))
      (node (ref "TP11") (pin "1") (pinfunction "=value_1") (pintype "passive"))
    )
    (net (code "37") (name "Net-(D1-Cathode)") (class "Default")
      (node (ref "D1") (pin "2") (pinfunction "Cathode_2") (pintype "passive"))
      (node (ref "Q1") (pin "1") (pinfunction "GATE_1") (pintype "passive"))
      (node (ref "R5") (pin "1") (pinfunction "1_1") (pintype "passive"))
    )
    (net (code "38") (name "Net-(D2-Cathode)") (class "Default")
      (node (ref "D2") (pin "2") (pinfunction "Cathode_2") (pintype "passive"))
      (node (ref "Q2") (pin "1") (pinfunction "GATE_1") (pintype "passive"))
      (node (ref "R6") (pin "1") (pinfunction "1_1") (pintype "passive"))
    )
    (net (code "39") (name "Net-(D3-Cathode)") (class "Default")
      (node (ref "D3") (pin "2") (pinfunction "Cathode_2") (pintype "passive"))
      (node (ref "Q3") (pin "1") (pinfunction "GATE_1") (pintype "passive"))
      (node (ref "R11") (pin "1") (pinfunction "1_1") (pintype "passive"))
    )
    (net (code "40") (name "Net-(D4-Cathode)") (class "Default")
      (node (ref "D4") (pin "2") (pinfunction "Cathode_2") (pintype "passive"))
      (node (ref "Q4") (pin "1") (pinfunction "GATE_1") (pintype "passive"))
      (node (ref "R12") (pin "1") (pinfunction "1_1") (pintype "passive"))
    )
    (net (code "41") (name "Net-(D5-Cathode)") (class "Default")
      (node (ref "D5") (pin "2") (pinfunction "Cathode_2") (pintype "passive"))
      (node (ref "Q5") (pin "1") (pinfunction "GATE_1") (pintype "passive"))
      (node (ref "R19") (pin "1") (pinfunction "1_1") (pintype "passive"))
    )
    (net (code "42") (name "Net-(D6-Cathode)") (class "Default")
      (node (ref "D6") (pin "2") (pinfunction "Cathode_2") (pintype "passive"))
      (node (ref "Q6") (pin "1") (pinfunction "GATE_1") (pintype "passive"))
      (node (ref "R20") (pin "1") (pinfunction "1_1") (pintype "passive"))
    )
    (net (code "43") (name "Net-(D7-Cathode)") (class "Default")
      (node (ref "D7") (pin "2") (pinfunction "Cathode_2") (pintype "passive"))
      (node (ref "Q7") (pin "1") (pinfunction "GATE_1") (pintype "passive"))
      (node (ref "R21") (pin "1") (pinfunction "1_1") (pintype "passive"))
    )
    (net (code "44") (name "Net-(D8-Cathode)") (class "Default")
      (node (ref "D8") (pin "2") (pinfunction "Cathode_2") (pintype "passive"))
      (node (ref "Q8") (pin "1") (pinfunction "GATE_1") (pintype "passive"))
      (node (ref "R28") (pin "1") (pinfunction "1_1") (pintype "passive"))
    )
    (net (code "45") (name "Net-(D9-Cathode)") (class "Default")
      (node (ref "D9") (pin "2") (pinfunction "Cathode_2") (pintype "passive"))
      (node (ref "Q9") (pin "1") (pinfunction "GATE_1") (pintype "passive"))
      (node (ref "R29") (pin "1") (pinfunction "1_1") (pintype "passive"))
    )
    (net (code "46") (name "Net-(D10-Cathode)") (class "Default")
      (node (ref "D10") (pin "2") (pinfunction "Cathode_2") (pintype "passive"))
      (node (ref "Q10") (pin "1") (pinfunction "GATE_1") (pintype "passive"))
      (node (ref "R30") (pin "1") (pinfunction "1_1") (pintype "passive"))
    )
    (net (code "47") (name "Net-(D11-Cathode)") (class "Default")
      (node (ref "D11") (pin "2") (pinfunction "Cathode_2") (pintype "passive"))
      (node (ref "Q11") (pin "1") (pinfunction "GATE_1") (pintype "passive"))
      (node (ref "R37") (pin "1") (pinfunction "1_1") (pintype "passive"))
    )
    (net (code "48") (name "Net-(D12-Cathode)") (class "Default")
      (node (ref "D12") (pin "2") (pinfunction "Cathode_2") (pintype "passive"))
      (node (ref "Q12") (pin "1") (pinfunction "GATE_1") (pintype "passive"))
      (node (ref "R38") (pin "1") (pinfunction "1_1") (pintype "passive"))
    )
    (net (code "49") (name "Net-(D13-Cathode)") (class "Default")
      (node (ref "D13") (pin "2") (pinfunction "Cathode_2") (pintype "passive"))
      (node (ref "Q13") (pin "1") (pinfunction "GATE_1") (pintype "passive"))
      (node (ref "R39") (pin "1") (pinfunction "1_1") (pintype "passive"))
    )
    (net (code "50") (name "Net-(D14-Cathode)") (class "Default")
      (node (ref "D14") (pin "2") (pinfunction "Cathode_2") (pintype "passive"))
      (node (ref "Q14") (pin "1") (pinfunction "GATE_1") (pintype "passive"))
      (node (ref "R45") (pin "1") (pinfunction "1_1") (pintype "passive"))
    )
    (net (code "51") (name "Net-(D15-Cathode)") (class "Default")
      (node (ref "D15") (pin "2") (pinfunction "Cathode_2") (pintype "passive"))
      (node (ref "Q15") (pin "1") (pinfunction "GATE_1") (pintype "passive"))
      (node (ref "R48") (pin "1") (pinfunction "1_1") (pintype "passive"))
    )
    (net (code "52") (name "Net-(D16-Cathode)") (class "Default")
      (node (ref "D16") (pin "2") (pinfunction "Cathode_2") (pintype "passive"))
      (node (ref "Q16") (pin "1") (pinfunction "GATE_1") (pintype "passive"))
      (node (ref "R55") (pin "1") (pinfunction "1_1") (pintype "passive"))
    )
    (net (code "53") (name "Net-(Q1-DRAIN)") (class "Default")
      (node (ref "Q1") (pin "3") (pinfunction "DRAIN_3") (pintype "passive"))
      (node (ref "R3") (pin "1") (pinfunction "1_1") (pintype "passive"))
    )
    (net (code "54") (name "Net-(Q2-DRAIN)") (class "Default")
      (node (ref "Q2") (pin "3") (pinfunction "DRAIN_3") (pintype "passive"))
      (node (ref "R4") (pin "1") (pinfunction "1_1") (pintype "passive"))
    )
    (net (code "55") (name "Net-(Q3-DRAIN)") (class "Default")
      (node (ref "Q3") (pin "3") (pinfunction "DRAIN_3") (pintype "passive"))
      (node (ref "R9") (pin "1") (pinfunction "1_1") (pintype "passive"))
    )
    (net (code "56") (name "Net-(Q4-DRAIN)") (class "Default")
      (node (ref "Q4") (pin "3") (pinfunction "DRAIN_3") (pintype "passive"))
      (node (ref "R10") (pin "1") (pinfunction "1_1") (pintype "passive"))
    )
    (net (code "57") (name "Net-(Q5-DRAIN)") (class "Default")
      (node (ref "Q5") (pin "3") (pinfunction "DRAIN_3") (pintype "passive"))
      (node (ref "R16") (pin "1") (pinfunction "1_1") (pintype "passive"))
    )
    (net (code "58") (name "Net-(Q6-DRAIN)") (class "Default")
      (node (ref "Q6") (pin "3") (pinfunction "DRAIN_3") (pintype "passive"))
      (node (ref "R17") (pin "1") (pinfunction "1_1") (pintype "passive"))
    )
    (net (code "59") (name "Net-(Q7-DRAIN)") (class "Default")
      (node (ref "Q7") (pin "3") (pinfunction "DRAIN_3") (pintype "passive"))
      (node (ref "R18") (pin "1") (pinfunction "1_1") (pintype "passive"))
    )
    (net (code "60") (name "Net-(Q8-DRAIN)") (class "Default")
      (node (ref "Q8") (pin "3") (pinfunction "DRAIN_3") (pintype "passive"))
      (node (ref "R25") (pin "1") (pinfunction "1_1") (pintype "passive"))
    )
    (net (code "61") (name "Net-(Q9-DRAIN)") (class "Default")
      (node (ref "Q9") (pin "3") (pinfunction "DRAIN_3") (pintype "passive"))
      (node (ref "R26") (pin "1") (pinfunction "1_1") (pintype "passive"))
    )
    (net (code "62") (name "Net-(Q10-DRAIN)") (class "Default")
      (node (ref "Q10") (pin "3") (pinfunction "DRAIN_3") (pintype "passive"))
      (node (ref "R27") (pin "1") (pinfunction "1_1") (pintype "passive"))
    )
    (net (code "63") (name "Net-(Q11-DRAIN)") (class "Default")
      (node (ref "Q11") (pin "3") (pinfunction "DRAIN_3") (pintype "passive"))
      (node (ref "R34") (pin "1") (pinfunction "1_1") (pintype "passive"))
    )
    (net (code "64") (name "Net-(Q12-DRAIN)") (class "Default")
      (node (ref "Q12") (pin "3") (pinfunction "DRAIN_3") (pintype "passive"))
      (node (ref "R35") (pin "1") (pinfunction "1_1") (pintype "passive"))
    )
    (net (code "65") (name "Net-(Q13-DRAIN)") (class "Default")
      (node (ref "Q13") (pin "3") (pinfunction "DRAIN_3") (pintype "passive"))
      (node (ref "R36") (pin "1") (pinfunction "1_1") (pintype "passive"))
    )
    (net (code "66") (name "Net-(Q14-DRAIN)") (class "Default")
      (node (ref "Q14") (pin "3") (pinfunction "DRAIN_3") (pintype "passive"))
      (node (ref "R43") (pin "1") (pinfunction "1_1") (pintype "passive"))
    )
    (net (code "67") (name "Net-(Q15-DRAIN)") (class "Default")
      (node (ref "Q15") (pin "3") (pinfunction "DRAIN_3") (pintype "passive"))
      (node (ref "R44") (pin "1") (pinfunction "1_1") (pintype "passive"))
    )
    (net (code "68") (name "Net-(Q16-DRAIN)") (class "Default")
      (node (ref "Q16") (pin "3") (pinfunction "DRAIN_3") (pintype "passive"))
      (node (ref "R54") (pin "1") (pinfunction "1_1") (pintype "passive"))
    )
    (net (code "69") (name "VBAT-") (class "Default")
      (node (ref "C13") (pin "1") (pinfunction "1_1") (pintype "passive"))
      (node (ref "C16") (pin "1") (pinfunction "1_1") (pintype "passive"))
    )
  )
)
